# CellSelectModule.net
KiCad netlist of a schematic drawn in Altium Designer
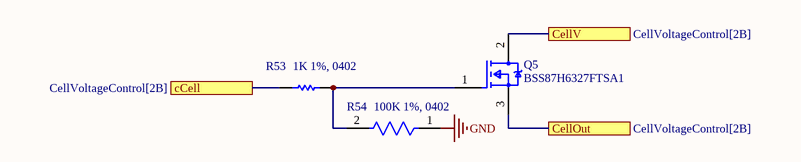
[diagram p0: CellSelectModule.SchDoc]

(export (version "E")
  (design (tool "Eeschema 10.0.6"))
  (components
    (comp (ref "Q5")
      (value "BSS87H6327FTSA1")
      (footprint "FP-PG-SOT89-4-MFG")
      (description "MOSFET N-CH 240V 260MA SOT89-4")
      (libsource (lib "Altium Content Vault") (part "0f782e8fd7e4ef74ecff6fccd0a82c3"))
    )
    (comp (ref "R53")
      (value "1K 1%, 0402")
      (footprint "RESC1005X40X25NL05T05")
      (description "Chip Resistor, 1 KOhm, +/- 1%, 100 mW, -55 to 155 degC, 0402 (1005 Metric), RoHS, Tape and Reel")
      (fields (field (name "PARTNUMBER") "ERJ-2RKF1001X") (field (name "MANUFACTURER") "Basic Passives"))
      (libsource (lib "Altium Content Vault") (part "RES-2"))
    )
    (comp (ref "R54")
      (value "100K 1%, 0402")
      (footprint "FP-ERJ2RK-IPC_C")
      (description "RES SMD 100K OHM 1% 1/10W 0402")
      (fields (field (name "TOLERANCE") "1%"))
      (libsource (lib "Altium Content Vault") (part "1029c3af85768c4190bb7ad29bc67b5"))
    )
  )
  (nets
    (net (code "1") (name "/CellOut") (class "Default")
      (node (ref "Q5") (pin "3") (pinfunction "Source_3") (pintype "passive"))
    )
    (net (code "2") (name "/CellV") (class "Default")
      (node (ref "Q5") (pin "2") (pinfunction "Drain_2") (pintype "passive"))
    )
    (net (code "3") (name "/cCell") (class "Default")
      (node (ref "R53") (pin "2") (pinfunction "2_2") (pintype "passive"))
    )
    (net (code "4") (name "GND") (class "Default")
      (node (ref "R54") (pin "1") (pinfunction "1_1") (pintype "passive"))
    )
    (net (code "5") (name "Net-(Q5-Gate)") (class "Default")
      (node (ref "Q5") (pin "1") (pinfunction "Gate_1") (pintype "passive"))
      (node (ref "R53") (pin "1") (pinfunction "1_1") (pintype "passive"))
      (node (ref "R54") (pin "2") (pinfunction "2_2") (pintype "passive"))
    )
  )
)
